# PolluxSensorBoard.net
KiCad netlist of a schematic drawn in EAGLE
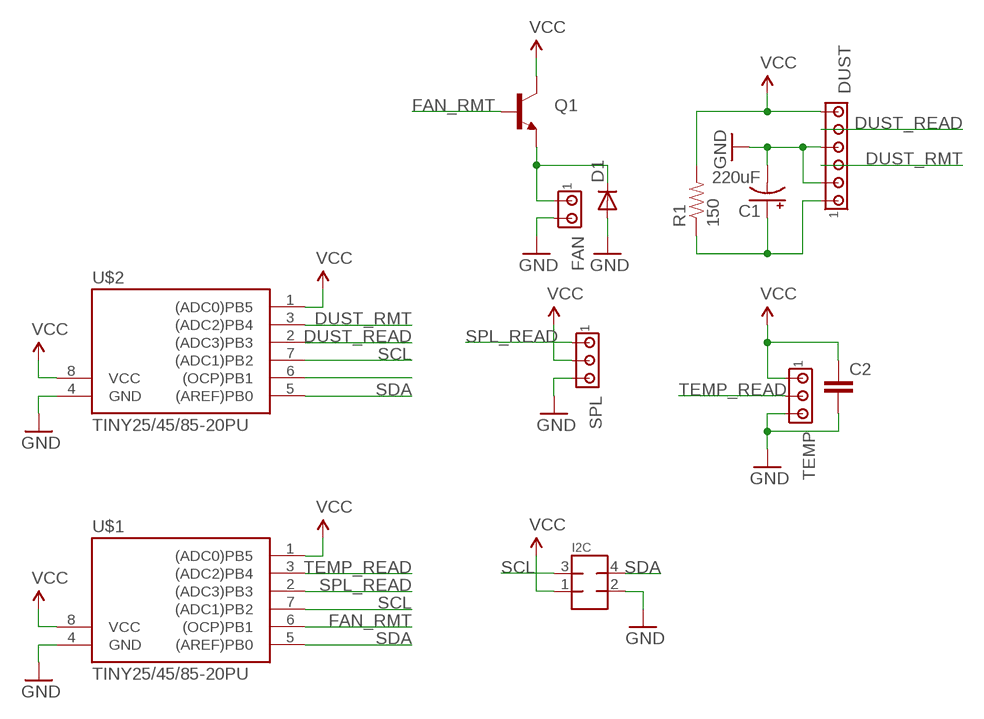
[diagram p0: schematic, sheet 1]

(export (version "E")
  (design (tool "Eeschema 10.0.6"))
  (components
    (comp (ref "C1")
      (value "220uF")
      (footprint "eagle-import:CPOL-RADIAL-1000UF-25V")
      (libsource (lib "eagle-import") (part "CAP_POLPTH4"))
    )
    (comp (ref "C2")
      (value "CAPPTH1")
      (footprint "eagle-import:CAP-PTH-5MM")
      (libsource (lib "eagle-import") (part "CAPPTH1"))
    )
    (comp (ref "D1")
      (value "DIODEPTH")
      (footprint "eagle-import:DIODE-1N4001")
      (libsource (lib "eagle-import") (part "DIODEPTH"))
    )
    (comp (ref "DUST")
      (value "MTA06-100")
      (footprint "eagle-import:10X06MTA")
      (libsource (lib "eagle-import") (part "MTA06-100"))
    )
    (comp (ref "FAN")
      (value "MTA02-100")
      (footprint "eagle-import:10X02MTA")
      (libsource (lib "eagle-import") (part "MTA02-100"))
    )
    (comp (ref "I2C")
      (value "MMATCH-8-PTH")
      (footprint "eagle-import:AMP-215079-8")
      (libsource (lib "eagle-import") (part "MMATCH-8-PTH"))
    )
    (comp (ref "Q1")
      (value "TRANSISTOR_NPNTO-92-AMMO")
      (footprint "eagle-import:TO-92-AMMO")
      (libsource (lib "eagle-import") (part "TRANSISTOR_NPNTO-92-AMMO"))
    )
    (comp (ref "R1")
      (value "150")
      (footprint "eagle-import:AXIAL-0.4")
      (libsource (lib "eagle-import") (part "RESISTORPTH-1/4W"))
    )
    (comp (ref "SPL")
      (value "MTA03-100")
      (footprint "eagle-import:10X03MTA")
      (libsource (lib "eagle-import") (part "MTA03-100"))
    )
    (comp (ref "TEMP")
      (value "MTA03-100")
      (footprint "eagle-import:10X03MTA")
      (libsource (lib "eagle-import") (part "MTA03-100"))
    )
    (comp (ref "U$1")
      (value "TINY25/45/85-20PU")
      (footprint "eagle-import:DIL08")
      (libsource (lib "eagle-import") (part "TINY25/45/85-20PU"))
    )
    (comp (ref "U$2")
      (value "TINY25/45/85-20PU")
      (footprint "eagle-import:DIL08")
      (libsource (lib "eagle-import") (part "TINY25/45/85-20PU"))
    )
  )
  (nets
    (net (code "1") (name "/DUST_READ") (class "Default")
      (node (ref "DUST") (pin "2") (pinfunction "5_2") (pintype "passive"))
      (node (ref "U$2") (pin "2") (pinfunction "(ADC3)PB3_2") (pintype "bidirectional"))
    )
    (net (code "2") (name "/DUST_RMT") (class "Default")
      (node (ref "DUST") (pin "4") (pinfunction "3_4") (pintype "passive"))
      (node (ref "U$2") (pin "3") (pinfunction "(ADC2)PB4_3") (pintype "bidirectional"))
    )
    (net (code "3") (name "/FAN_RMT") (class "Default")
      (node (ref "Q1") (pin "2") (pinfunction "B_2") (pintype "passive"))
      (node (ref "U$1") (pin "6") (pinfunction "(OCP)PB1_6") (pintype "bidirectional"))
    )
    (net (code "4") (name "/SCL") (class "Default")
      (node (ref "I2C") (pin "3") (pinfunction "3_3") (pintype "bidirectional"))
      (node (ref "U$1") (pin "7") (pinfunction "(ADC1)PB2_7") (pintype "bidirectional"))
      (node (ref "U$2") (pin "7") (pinfunction "(ADC1)PB2_7") (pintype "bidirectional"))
    )
    (net (code "5") (name "/SDA") (class "Default")
      (node (ref "I2C") (pin "4") (pinfunction "4_4") (pintype "bidirectional"))
      (node (ref "U$1") (pin "5") (pinfunction "(AREF)PB0_5") (pintype "bidirectional"))
      (node (ref "U$2") (pin "5") (pinfunction "(AREF)PB0_5") (pintype "bidirectional"))
    )
    (net (code "6") (name "/SPL_READ") (class "Default")
      (node (ref "SPL") (pin "1") (pinfunction "1_1") (pintype "passive"))
      (node (ref "U$1") (pin "2") (pinfunction "(ADC3)PB3_2") (pintype "bidirectional"))
    )
    (net (code "7") (name "/TEMP_READ") (class "Default")
      (node (ref "TEMP") (pin "2") (pinfunction "2_2") (pintype "passive"))
      (node (ref "U$1") (pin "3") (pinfunction "(ADC2)PB4_3") (pintype "bidirectional"))
    )
    (net (code "8") (name "GND") (class "Default")
      (node (ref "C1") (pin "2") (pinfunction "-_2") (pintype "passive"))
      (node (ref "C2") (pin "2") (pinfunction "2_2") (pintype "passive"))
      (node (ref "D1") (pin "A") (pinfunction "A_A") (pintype "passive"))
      (node (ref "DUST") (pin "3") (pinfunction "4_3") (pintype "passive"))
      (node (ref "DUST") (pin "5") (pinfunction "2_5") (pintype "passive"))
      (node (ref "FAN") (pin "2") (pinfunction "2_2") (pintype "passive"))
      (node (ref "I2C") (pin "2") (pinfunction "2_2") (pintype "bidirectional"))
      (node (ref "SPL") (pin "3") (pinfunction "3_3") (pintype "passive"))
      (node (ref "TEMP") (pin "3") (pinfunction "3_3") (pintype "passive"))
      (node (ref "U$1") (pin "4") (pinfunction "GND_4") (pintype "power_in"))
      (node (ref "U$2") (pin "4") (pinfunction "GND_4") (pintype "power_in"))
    )
    (net (code "9") (name "Net-(C1-+)") (class "Default")
      (node (ref "C1") (pin "1") (pinfunction "+_1") (pintype "passive"))
      (node (ref "DUST") (pin "6") (pinfunction "1_6") (pintype "passive"))
      (node (ref "R1") (pin "P$1") (pinfunction "1_P$1") (pintype "passive"))
    )
    (net (code "10") (name "Net-(Q1-E)") (class "Default")
      (node (ref "D1") (pin "C") (pinfunction "C_C") (pintype "passive"))
      (node (ref "FAN") (pin "1") (pinfunction "1_1") (pintype "passive"))
      (node (ref "Q1") (pin "1") (pinfunction "E_1") (pintype "passive"))
    )
    (net (code "11") (name "VCC") (class "Default")
      (node (ref "C2") (pin "1") (pinfunction "1_1") (pintype "passive"))
      (node (ref "DUST") (pin "1") (pinfunction "6_1") (pintype "passive"))
      (node (ref "I2C") (pin "1") (pinfunction "1_1") (pintype "bidirectional"))
      (node (ref "Q1") (pin "3") (pinfunction "C_3") (pintype "passive"))
      (node (ref "R1") (pin "P$2") (pinfunction "2_P$2") (pintype "passive"))
      (node (ref "SPL") (pin "2") (pinfunction "2_2") (pintype "passive"))
      (node (ref "TEMP") (pin "1") (pinfunction "1_1") (pintype "passive"))
      (node (ref "U$1") (pin "1") (pinfunction "(ADC0)PB5_1") (pintype "bidirectional"))
      (node (ref "U$1") (pin "8") (pinfunction "VCC_8") (pintype "power_in"))
      (node (ref "U$2") (pin "1") (pinfunction "(ADC0)PB5_1") (pintype "bidirectional"))
      (node (ref "U$2") (pin "8") (pinfunction "VCC_8") (pintype "power_in"))
    )
    (net (code "12") (name "unconnected-(U$2-(OCP)PB1-Pad6)") (class "Default")
      (node (ref "U$2") (pin "6") (pinfunction "(OCP)PB1_6") (pintype "bidirectional"))
    )
  )
)
